# Mind-Synchronizing-Generator-PinHdrPotX-.net
KiCad netlist of a schematic drawn in EAGLE
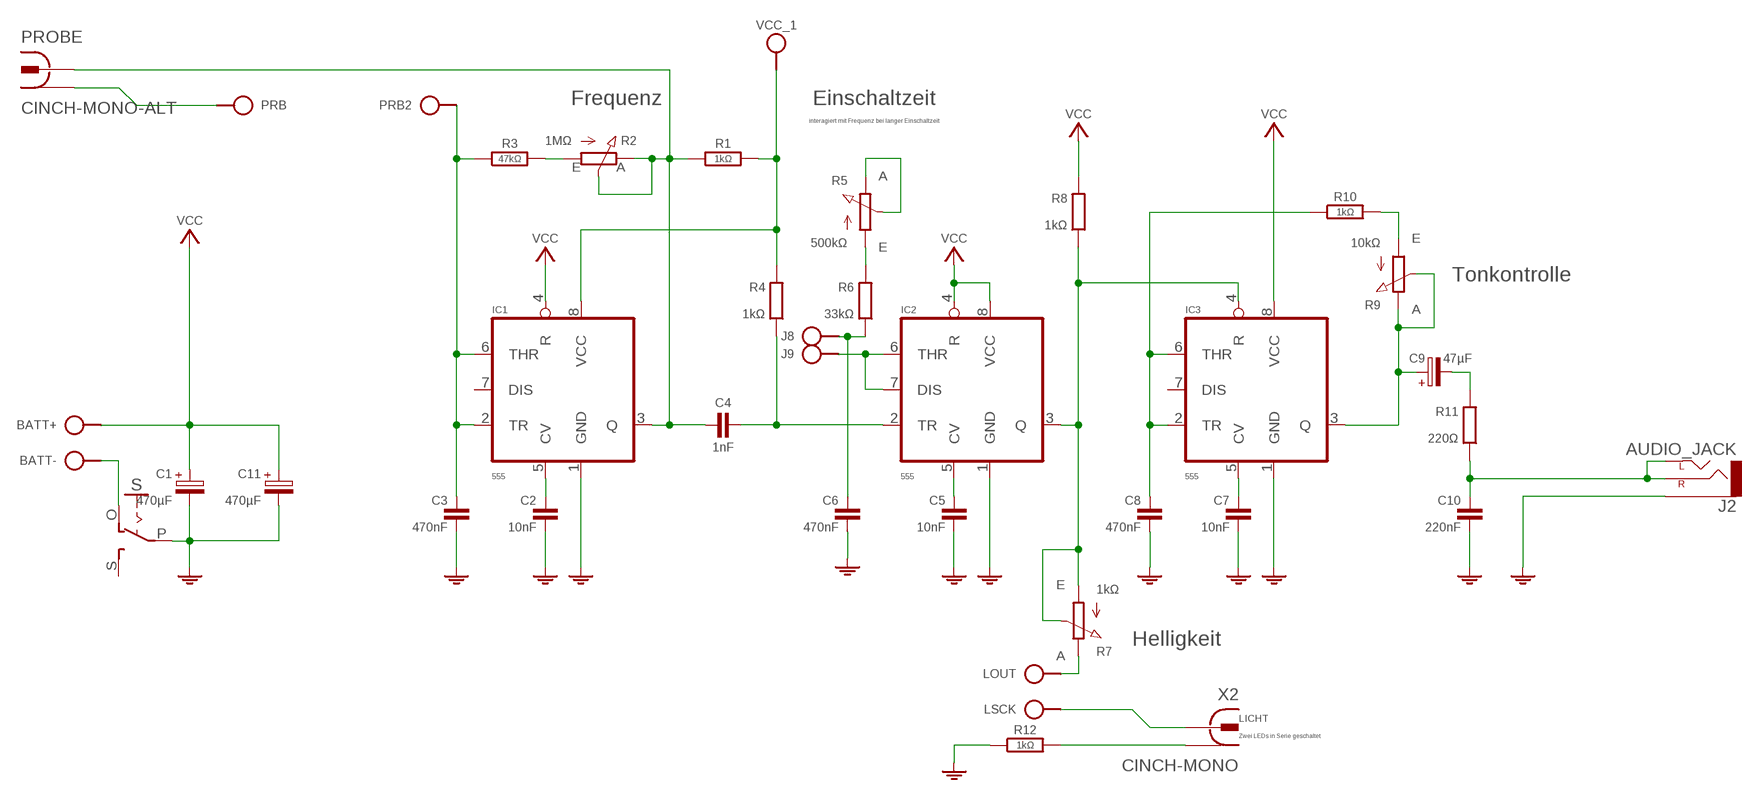
[diagram p0: schematic, sheet 1]

(export (version "E")
  (design (tool "Eeschema 10.0.6"))
  (components
    (comp (ref "BATT")
      (value "SPAD+--+")
      (footprint "eagle-import:SPAD-+")
      (libsource (lib "eagle-import") (part "SPAD+--+"))
    )
    (comp (ref "C1")
      (value "470µF")
      (footprint "eagle-import:E2,5-6")
      (libsource (lib "eagle-import") (part "CPOLE2.5-6"))
    )
    (comp (ref "C2")
      (value "10nF")
      (footprint "eagle-import:C050-020X044")
      (libsource (lib "eagle-import") (part "C050-020X044"))
    )
    (comp (ref "C3")
      (value "470nF")
      (footprint "eagle-import:C050-040X075")
      (libsource (lib "eagle-import") (part "C050-040X075"))
    )
    (comp (ref "C4")
      (value "1nF")
      (footprint "eagle-import:C050-020X044")
      (libsource (lib "eagle-import") (part "C-H050-020X044"))
    )
    (comp (ref "C5")
      (value "10nF")
      (footprint "eagle-import:C050-020X044_V")
      (libsource (lib "eagle-import") (part "C050-020X044/V"))
    )
    (comp (ref "C6")
      (value "470nF")
      (footprint "eagle-import:C050-040X075")
      (libsource (lib "eagle-import") (part "C050-040X075"))
    )
    (comp (ref "C7")
      (value "10nF")
      (footprint "eagle-import:C050-020X044_V")
      (libsource (lib "eagle-import") (part "C050-020X044/V"))
    )
    (comp (ref "C8")
      (value "470nF")
      (footprint "eagle-import:C050-040X075")
      (libsource (lib "eagle-import") (part "C050-040X075"))
    )
    (comp (ref "C9")
      (value "47µF")
      (footprint "eagle-import:E2,5-4")
      (libsource (lib "eagle-import") (part "CPOL-HE2,5-4"))
    )
    (comp (ref "C10")
      (value "220nF")
      (footprint "eagle-import:C050-025X060")
      (libsource (lib "eagle-import") (part "C025-025X060"))
    )
    (comp (ref "C11")
      (value "470µF")
      (footprint "eagle-import:E2,5-6")
      (libsource (lib "eagle-import") (part "CPOLE2.5-6"))
    )
    (comp (ref "IC1")
      (value "555")
      (footprint "eagle-import:555-DIL")
      (libsource (lib "eagle-import") (part "555_ALT2-LBL"))
    )
    (comp (ref "IC2")
      (value "555")
      (footprint "eagle-import:555-DIL")
      (libsource (lib "eagle-import") (part "555_ALT2-LBL"))
    )
    (comp (ref "IC3")
      (value "555")
      (footprint "eagle-import:555-DIL")
      (libsource (lib "eagle-import") (part "555_ALT2-LBL"))
    )
    (comp (ref "J2")
      (value "AUDIO_JACK")
      (footprint "eagle-import:AUDIO-JACK")
      (libsource (lib "eagle-import") (part "AUDIO_JACK"))
    )
    (comp (ref "J8")
      (value "HPORT")
      (footprint "eagle-import:SPAD")
      (libsource (lib "eagle-import") (part "HPORT"))
    )
    (comp (ref "J9")
      (value "HPORT")
      (footprint "eagle-import:SPAD")
      (libsource (lib "eagle-import") (part "HPORT"))
    )
    (comp (ref "LOUT")
      (value "HPORT")
      (footprint "eagle-import:SPAD")
      (libsource (lib "eagle-import") (part "HPORT"))
    )
    (comp (ref "LSCK")
      (value "HPORT")
      (footprint "eagle-import:SPAD")
      (libsource (lib "eagle-import") (part "HPORT"))
    )
    (comp (ref "PRB")
      (value "HPORT")
      (footprint "eagle-import:SPAD")
      (libsource (lib "eagle-import") (part "HPORT"))
    )
    (comp (ref "PRB2")
      (value "HPORT")
      (footprint "eagle-import:SPAD")
      (libsource (lib "eagle-import") (part "HPORT"))
    )
    (comp (ref "PROBE")
      (value "CINCH-MONO-ALT")
      (footprint "eagle-import:736880-49")
      (libsource (lib "eagle-import") (part "CINCH-MONO-ALT"))
    )
    (comp (ref "R1")
      (value "1kΩ")
      (footprint "eagle-import:0204_10")
      (libsource (lib "eagle-import") (part "R-H0204/10"))
    )
    (comp (ref "R2")
      (value "1MΩ")
      (footprint "eagle-import:CONN-3P")
      (libsource (lib "eagle-import") (part "POT-H-3P"))
    )
    (comp (ref "R3")
      (value "47kΩ")
      (footprint "eagle-import:0204_10")
      (libsource (lib "eagle-import") (part "R-H0204/10"))
    )
    (comp (ref "R4")
      (value "1kΩ")
      (footprint "eagle-import:0204_10-V")
      (libsource (lib "eagle-import") (part "R0204/10-V"))
    )
    (comp (ref "R5")
      (value "500kΩ")
      (footprint "eagle-import:CONN-3P")
      (libsource (lib "eagle-import") (part "POT-3P"))
    )
    (comp (ref "R6")
      (value "33kΩ")
      (footprint "eagle-import:0204_10")
      (libsource (lib "eagle-import") (part "R0204/10"))
    )
    (comp (ref "R7")
      (value "1kΩ")
      (footprint "eagle-import:CONN-3P")
      (libsource (lib "eagle-import") (part "POT-3P-S1"))
    )
    (comp (ref "R8")
      (value "1kΩ")
      (footprint "eagle-import:0204_10-V")
      (libsource (lib "eagle-import") (part "R0204/10-V"))
    )
    (comp (ref "R9")
      (value "10kΩ")
      (footprint "eagle-import:CONN-3P")
      (libsource (lib "eagle-import") (part "POT-3P"))
    )
    (comp (ref "R10")
      (value "1kΩ")
      (footprint "eagle-import:0204_10")
      (libsource (lib "eagle-import") (part "R-H0204/10"))
    )
    (comp (ref "R11")
      (value "220Ω")
      (footprint "eagle-import:0204_10-V")
      (libsource (lib "eagle-import") (part "R0204/10-V"))
    )
    (comp (ref "R12")
      (value "1kΩ")
      (footprint "eagle-import:0204_10")
      (libsource (lib "eagle-import") (part "R-H0204/10"))
    )
    (comp (ref "S")
      (value "SL-SW-1P-2T-H")
      (footprint "eagle-import:SLSW-1P2T-H")
      (libsource (lib "eagle-import") (part "SL-SW-1P-2T-H"))
    )
    (comp (ref "VCC_1")
      (value "VPORT")
      (footprint "eagle-import:SPAD")
      (libsource (lib "eagle-import") (part "VPORT"))
    )
    (comp (ref "X2")
      (value "CINCH-MONO")
      (footprint "eagle-import:736880-49")
      (libsource (lib "eagle-import") (part "CINCH-MONO"))
    )
  )
  (nets
    (net (code "1") (name "GND") (class "Default")
      (node (ref "C1") (pin "-") (pinfunction "-_-") (pintype "passive"))
      (node (ref "C10") (pin "2") (pinfunction "2_2") (pintype "passive"))
      (node (ref "C11") (pin "-") (pinfunction "-_-") (pintype "passive"))
      (node (ref "C2") (pin "2") (pinfunction "2_2") (pintype "passive"))
      (node (ref "C3") (pin "2") (pinfunction "2_2") (pintype "passive"))
      (node (ref "C5") (pin "2") (pinfunction "2_2") (pintype "passive"))
      (node (ref "C6") (pin "2") (pinfunction "2_2") (pintype "passive"))
      (node (ref "C7") (pin "2") (pinfunction "2_2") (pintype "passive"))
      (node (ref "C8") (pin "2") (pinfunction "2_2") (pintype "passive"))
      (node (ref "IC1") (pin "1") (pinfunction "GND_1") (pintype "power_in"))
      (node (ref "IC2") (pin "1") (pinfunction "GND_1") (pintype "power_in"))
      (node (ref "IC3") (pin "1") (pinfunction "GND_1") (pintype "power_in"))
      (node (ref "J2") (pin "SLEEVE") (pinfunction "SLEEVE_SLEEVE") (pintype "bidirectional"))
      (node (ref "R12") (pin "1") (pinfunction "1_1") (pintype "passive"))
      (node (ref "S") (pin "P") (pinfunction "P_P") (pintype "passive"))
    )
    (net (code "2") (name "Net-(BATTB-P$1)") (class "Default")
      (node (ref "BATT") (pin "1") (pinfunction "P$1_1") (pintype "passive"))
      (node (ref "S") (pin "O") (pinfunction "O_O") (pintype "passive"))
    )
    (net (code "3") (name "Net-(IC1-CV)") (class "Default")
      (node (ref "C2") (pin "1") (pinfunction "1_1") (pintype "passive"))
      (node (ref "IC1") (pin "5") (pinfunction "CV_5") (pintype "input"))
    )
    (net (code "4") (name "Net-(IC1-Q)") (class "Default")
      (node (ref "C4") (pin "1") (pinfunction "1_1") (pintype "passive"))
      (node (ref "IC1") (pin "3") (pinfunction "Q_3") (pintype "output"))
      (node (ref "PROBE") (pin "1@2") (pinfunction "2_1@2") (pintype "passive"))
      (node (ref "R1") (pin "1") (pinfunction "1_1") (pintype "passive"))
      (node (ref "R2") (pin "2") (pinfunction "S_2") (pintype "passive"))
      (node (ref "R2") (pin "3") (pinfunction "E_3") (pintype "passive"))
    )
    (net (code "5") (name "Net-(IC1-THR)") (class "Default")
      (node (ref "C3") (pin "1") (pinfunction "1_1") (pintype "passive"))
      (node (ref "IC1") (pin "2") (pinfunction "TR_2") (pintype "input"))
      (node (ref "IC1") (pin "6") (pinfunction "THR_6") (pintype "input"))
      (node (ref "PRB2") (pin "1") (pinfunction "P$1_1") (pintype "passive"))
      (node (ref "R3") (pin "1") (pinfunction "1_1") (pintype "passive"))
    )
    (net (code "6") (name "Net-(IC1-VCC)") (class "Default")
      (node (ref "IC1") (pin "8") (pinfunction "VCC_8") (pintype "power_in"))
      (node (ref "R1") (pin "2") (pinfunction "2_2") (pintype "passive"))
      (node (ref "R4") (pin "1") (pinfunction "2_1") (pintype "passive"))
      (node (ref "VCC_1") (pin "1") (pinfunction "P$1_1") (pintype "passive"))
    )
    (net (code "7") (name "Net-(IC2-CV)") (class "Default")
      (node (ref "C5") (pin "1") (pinfunction "1_1") (pintype "passive"))
      (node (ref "IC2") (pin "5") (pinfunction "CV_5") (pintype "input"))
    )
    (net (code "8") (name "Net-(IC2-DIS)") (class "Default")
      (node (ref "IC2") (pin "6") (pinfunction "THR_6") (pintype "input"))
      (node (ref "IC2") (pin "7") (pinfunction "DIS_7") (pintype "passive"))
      (node (ref "J9") (pin "1") (pinfunction "P$1_1") (pintype "passive"))
    )
    (net (code "9") (name "Net-(IC2-Q)") (class "Default")
      (node (ref "IC2") (pin "3") (pinfunction "Q_3") (pintype "output"))
      (node (ref "IC3") (pin "4") (pinfunction "R_4") (pintype "input"))
      (node (ref "R7") (pin "1") (pinfunction "S_1") (pintype "passive"))
      (node (ref "R7") (pin "2") (pinfunction "A_2") (pintype "passive"))
      (node (ref "R8") (pin "2") (pinfunction "1_2") (pintype "passive"))
    )
    (net (code "10") (name "Net-(IC2-TR)") (class "Default")
      (node (ref "C4") (pin "2") (pinfunction "2_2") (pintype "passive"))
      (node (ref "IC2") (pin "2") (pinfunction "TR_2") (pintype "input"))
      (node (ref "R4") (pin "2") (pinfunction "1_2") (pintype "passive"))
    )
    (net (code "11") (name "Net-(IC3-CV)") (class "Default")
      (node (ref "C7") (pin "1") (pinfunction "1_1") (pintype "passive"))
      (node (ref "IC3") (pin "5") (pinfunction "CV_5") (pintype "input"))
    )
    (net (code "12") (name "Net-(IC3-Q)") (class "Default")
      (node (ref "C9") (pin "+") (pinfunction "+_+") (pintype "passive"))
      (node (ref "IC3") (pin "3") (pinfunction "Q_3") (pintype "output"))
      (node (ref "R9") (pin "2") (pinfunction "S_2") (pintype "passive"))
      (node (ref "R9") (pin "3") (pinfunction "E_3") (pintype "passive"))
    )
    (net (code "13") (name "Net-(IC3-THR)") (class "Default")
      (node (ref "C8") (pin "1") (pinfunction "1_1") (pintype "passive"))
      (node (ref "IC3") (pin "2") (pinfunction "TR_2") (pintype "input"))
      (node (ref "IC3") (pin "6") (pinfunction "THR_6") (pintype "input"))
      (node (ref "R10") (pin "1") (pinfunction "1_1") (pintype "passive"))
    )
    (net (code "14") (name "Net-(J2-LEFT)") (class "Default")
      (node (ref "C10") (pin "1") (pinfunction "1_1") (pintype "passive"))
      (node (ref "J2") (pin "RING") (pinfunction "RIGHT_RING") (pintype "bidirectional"))
      (node (ref "J2") (pin "TIP") (pinfunction "LEFT_TIP") (pintype "bidirectional"))
      (node (ref "R11") (pin "2") (pinfunction "1_2") (pintype "passive"))
    )
    (net (code "15") (name "Net-(J8-P$1)") (class "Default")
      (node (ref "C6") (pin "1") (pinfunction "1_1") (pintype "passive"))
      (node (ref "J8") (pin "1") (pinfunction "P$1_1") (pintype "passive"))
      (node (ref "R6") (pin "2") (pinfunction "1_2") (pintype "passive"))
    )
    (net (code "16") (name "Net-(LOUT-P$1)") (class "Default")
      (node (ref "LOUT") (pin "1") (pinfunction "P$1_1") (pintype "passive"))
      (node (ref "R7") (pin "3") (pinfunction "E_3") (pintype "passive"))
    )
    (net (code "17") (name "Net-(LSCK-P$1)") (class "Default")
      (node (ref "LSCK") (pin "1") (pinfunction "P$1_1") (pintype "passive"))
      (node (ref "X2") (pin "1@1") (pinfunction "2_1@1") (pintype "passive"))
    )
    (net (code "18") (name "Net-(PRB-P$1)") (class "Default")
      (node (ref "PRB") (pin "1") (pinfunction "P$1_1") (pintype "passive"))
      (node (ref "PROBE") (pin "1") (pinfunction "1_1") (pintype "passive"))
    )
    (net (code "19") (name "Net-(R2-A)") (class "Default")
      (node (ref "R2") (pin "1") (pinfunction "A_1") (pintype "passive"))
      (node (ref "R3") (pin "2") (pinfunction "2_2") (pintype "passive"))
    )
    (net (code "20") (name "Net-(R5-A)") (class "Default")
      (node (ref "R5") (pin "1") (pinfunction "A_1") (pintype "passive"))
      (node (ref "R6") (pin "1") (pinfunction "2_1") (pintype "passive"))
    )
    (net (code "21") (name "Net-(R9-A)") (class "Default")
      (node (ref "R10") (pin "2") (pinfunction "2_2") (pintype "passive"))
      (node (ref "R9") (pin "1") (pinfunction "A_1") (pintype "passive"))
    )
    (net (code "22") (name "Net-(R11-2)") (class "Default")
      (node (ref "C9") (pin "-") (pinfunction "-_-") (pintype "passive"))
      (node (ref "R11") (pin "1") (pinfunction "2_1") (pintype "passive"))
    )
    (net (code "23") (name "Net-(R12-Pad2)") (class "Default")
      (node (ref "R12") (pin "2") (pinfunction "2_2") (pintype "passive"))
      (node (ref "X2") (pin "1") (pinfunction "1_1") (pintype "passive"))
    )
    (net (code "24") (name "VCC") (class "Default")
      (node (ref "BATT") (pin "2") (pinfunction "P$1_2") (pintype "passive"))
      (node (ref "C1") (pin "+") (pinfunction "+_+") (pintype "passive"))
      (node (ref "C11") (pin "+") (pinfunction "+_+") (pintype "passive"))
      (node (ref "IC1") (pin "4") (pinfunction "R_4") (pintype "input"))
      (node (ref "IC2") (pin "4") (pinfunction "R_4") (pintype "input"))
      (node (ref "IC2") (pin "8") (pinfunction "VCC_8") (pintype "power_in"))
      (node (ref "IC3") (pin "8") (pinfunction "VCC_8") (pintype "power_in"))
      (node (ref "R5") (pin "2") (pinfunction "S_2") (pintype "passive"))
      (node (ref "R5") (pin "3") (pinfunction "E_3") (pintype "passive"))
      (node (ref "R8") (pin "1") (pinfunction "2_1") (pintype "passive"))
    )
    (net (code "25") (name "unconnected-(IC1-DIS-Pad7)") (class "Default")
      (node (ref "IC1") (pin "7") (pinfunction "DIS_7") (pintype "passive"))
    )
    (net (code "26") (name "unconnected-(IC3-DIS-Pad7)") (class "Default")
      (node (ref "IC3") (pin "7") (pinfunction "DIS_7") (pintype "passive"))
    )
    (net (code "27") (name "unconnected-(S-PadS)") (class "Default")
      (node (ref "S") (pin "S") (pinfunction "S_S") (pintype "passive"))
    )
  )
)
